# Paulo.net
KiCad netlist of a schematic drawn in EAGLE
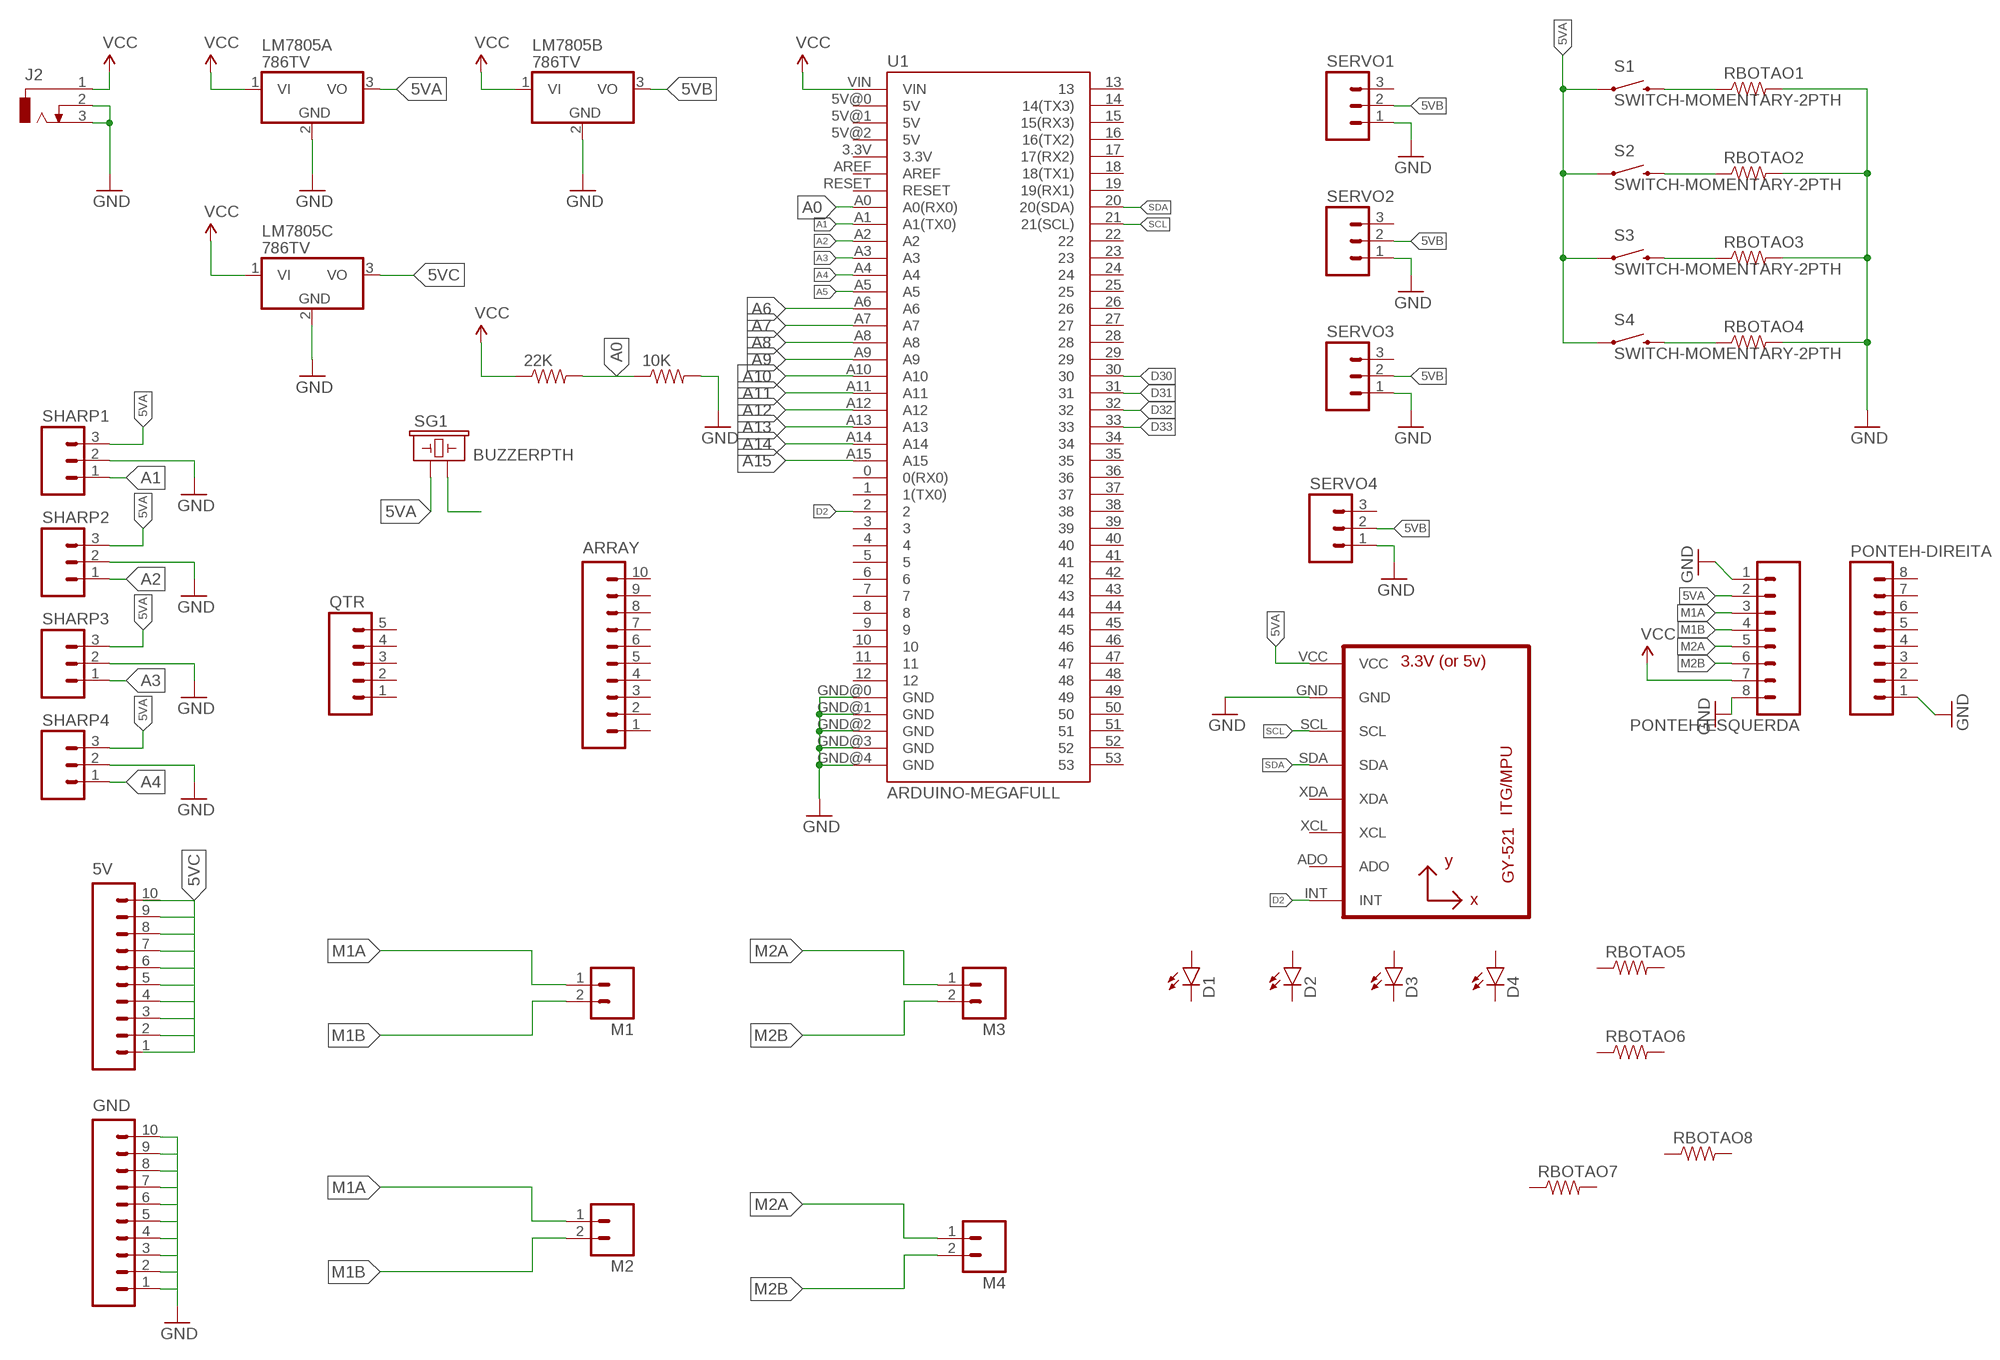
[diagram p0: schematic, sheet 1]

(export (version "E")
  (design (tool "Eeschema 10.0.6"))
  (components
    (comp (ref "5V")
      (value "M10SILK_FEMALE_PTH")
      (footprint "eagle-import:1X10")
      (libsource (lib "eagle-import") (part "M10SILK_FEMALE_PTH"))
    )
    (comp (ref "10K")
      (value "RESISTOREZ")
      (footprint "eagle-import:AXIAL-0.3EZ")
      (libsource (lib "eagle-import") (part "RESISTOREZ"))
    )
    (comp (ref "22K")
      (value "RESISTOREZ")
      (footprint "eagle-import:AXIAL-0.3EZ")
      (libsource (lib "eagle-import") (part "RESISTOREZ"))
    )
    (comp (ref "ARRAY")
      (value "M10SILK_FEMALE_PTH")
      (footprint "eagle-import:1X10")
      (libsource (lib "eagle-import") (part "M10SILK_FEMALE_PTH"))
    )
    (comp (ref "D1")
      (value "LED5MM")
      (footprint "eagle-import:LED5MM")
      (libsource (lib "eagle-import") (part "LED5MM"))
    )
    (comp (ref "D2")
      (value "LED5MM")
      (footprint "eagle-import:LED5MM")
      (libsource (lib "eagle-import") (part "LED5MM"))
    )
    (comp (ref "D3")
      (value "LED5MM")
      (footprint "eagle-import:LED5MM")
      (libsource (lib "eagle-import") (part "LED5MM"))
    )
    (comp (ref "D4")
      (value "LED5MM")
      (footprint "eagle-import:LED5MM")
      (libsource (lib "eagle-import") (part "LED5MM"))
    )
    (comp (ref "GND")
      (value "M10SILK_FEMALE_PTH")
      (footprint "eagle-import:1X10")
      (libsource (lib "eagle-import") (part "M10SILK_FEMALE_PTH"))
    )
    (comp (ref "J2")
      (value "DCJ0303")
      (footprint "eagle-import:DCJ0303")
      (libsource (lib "eagle-import") (part "DCJ0303"))
    )
    (comp (ref "LM7805A")
      (value "786TV")
      (footprint "eagle-import:TO220V")
      (libsource (lib "eagle-import") (part "78TV6"))
    )
    (comp (ref "LM7805B")
      (value "786TV")
      (footprint "eagle-import:TO220V")
      (libsource (lib "eagle-import") (part "78TV6"))
    )
    (comp (ref "LM7805C")
      (value "786TV")
      (footprint "eagle-import:TO220V")
      (libsource (lib "eagle-import") (part "78TV6"))
    )
    (comp (ref "M1")
      (value "M02JST-PTH-VERT")
      (footprint "eagle-import:JST-2-PTH-VERT")
      (libsource (lib "eagle-import") (part "M02JST-PTH-VERT"))
    )
    (comp (ref "M2")
      (value "M02JST-PTH-VERT")
      (footprint "eagle-import:JST-2-PTH-VERT")
      (libsource (lib "eagle-import") (part "M02JST-PTH-VERT"))
    )
    (comp (ref "M3")
      (value "M02JST-PTH-VERT")
      (footprint "eagle-import:JST-2-PTH-VERT")
      (libsource (lib "eagle-import") (part "M02JST-PTH-VERT"))
    )
    (comp (ref "M4")
      (value "M02JST-PTH-VERT")
      (footprint "eagle-import:JST-2-PTH-VERT")
      (libsource (lib "eagle-import") (part "M02JST-PTH-VERT"))
    )
    (comp (ref "PONTEH-DIREITA")
      (value "M08NO_SILK")
      (footprint "eagle-import:1X08_PIN1_NO_SILK")
      (libsource (lib "eagle-import") (part "M08NO_SILK"))
    )
    (comp (ref "PONTEH-ESQUERDA")
      (value "M08NO_SILK")
      (footprint "eagle-import:1X08_PIN1_NO_SILK")
      (libsource (lib "eagle-import") (part "M08NO_SILK"))
    )
    (comp (ref "QTR")
      (value "M05PTH_LONGPADS")
      (footprint "eagle-import:1X05_LONGPADS")
      (libsource (lib "eagle-import") (part "M05PTH_LONGPADS"))
    )
    (comp (ref "RBOTAO1")
      (value "RESISTOREZ")
      (footprint "eagle-import:AXIAL-0.3EZ")
      (libsource (lib "eagle-import") (part "RESISTOREZ"))
    )
    (comp (ref "RBOTAO2")
      (value "RESISTOREZ")
      (footprint "eagle-import:AXIAL-0.3EZ")
      (libsource (lib "eagle-import") (part "RESISTOREZ"))
    )
    (comp (ref "RBOTAO3")
      (value "RESISTOREZ")
      (footprint "eagle-import:AXIAL-0.3EZ")
      (libsource (lib "eagle-import") (part "RESISTOREZ"))
    )
    (comp (ref "RBOTAO4")
      (value "RESISTOREZ")
      (footprint "eagle-import:AXIAL-0.3EZ")
      (libsource (lib "eagle-import") (part "RESISTOREZ"))
    )
    (comp (ref "RBOTAO5")
      (value "RESISTOREZ")
      (footprint "eagle-import:AXIAL-0.3EZ")
      (libsource (lib "eagle-import") (part "RESISTOREZ"))
    )
    (comp (ref "RBOTAO6")
      (value "RESISTOREZ")
      (footprint "eagle-import:AXIAL-0.3EZ")
      (libsource (lib "eagle-import") (part "RESISTOREZ"))
    )
    (comp (ref "RBOTAO7")
      (value "RESISTOREZ")
      (footprint "eagle-import:AXIAL-0.3EZ")
      (libsource (lib "eagle-import") (part "RESISTOREZ"))
    )
    (comp (ref "RBOTAO8")
      (value "RESISTOREZ")
      (footprint "eagle-import:AXIAL-0.3EZ")
      (libsource (lib "eagle-import") (part "RESISTOREZ"))
    )
    (comp (ref "S1")
      (value "SWITCH-MOMENTARY-2PTH")
      (footprint "eagle-import:TACTILE-PTH")
      (libsource (lib "eagle-import") (part "SWITCH-MOMENTARY-2PTH"))
    )
    (comp (ref "S2")
      (value "SWITCH-MOMENTARY-2PTH")
      (footprint "eagle-import:TACTILE-PTH")
      (libsource (lib "eagle-import") (part "SWITCH-MOMENTARY-2PTH"))
    )
    (comp (ref "S3")
      (value "SWITCH-MOMENTARY-2PTH")
      (footprint "eagle-import:TACTILE-PTH")
      (libsource (lib "eagle-import") (part "SWITCH-MOMENTARY-2PTH"))
    )
    (comp (ref "S4")
      (value "SWITCH-MOMENTARY-2PTH")
      (footprint "eagle-import:TACTILE-PTH")
      (libsource (lib "eagle-import") (part "SWITCH-MOMENTARY-2PTH"))
    )
    (comp (ref "SERVO1")
      (value "M03LONGPADS")
      (footprint "eagle-import:1X03_LONGPADS")
      (libsource (lib "eagle-import") (part "M03LONGPADS"))
    )
    (comp (ref "SERVO2")
      (value "M03LONGPADS")
      (footprint "eagle-import:1X03_LONGPADS")
      (libsource (lib "eagle-import") (part "M03LONGPADS"))
    )
    (comp (ref "SERVO3")
      (value "M03LONGPADS")
      (footprint "eagle-import:1X03_LONGPADS")
      (libsource (lib "eagle-import") (part "M03LONGPADS"))
    )
    (comp (ref "SERVO4")
      (value "M03LONGPADS")
      (footprint "eagle-import:1X03_LONGPADS")
      (libsource (lib "eagle-import") (part "M03LONGPADS"))
    )
    (comp (ref "SG1")
      (value "BUZZERPTH")
      (footprint "eagle-import:BUZZER-12MM")
      (libsource (lib "eagle-import") (part "BUZZERPTH"))
    )
    (comp (ref "SHARP1")
      (value "M03LONGPADS")
      (footprint "eagle-import:1X03_LONGPADS")
      (libsource (lib "eagle-import") (part "M03LONGPADS"))
    )
    (comp (ref "SHARP2")
      (value "M03LONGPADS")
      (footprint "eagle-import:1X03_LONGPADS")
      (libsource (lib "eagle-import") (part "M03LONGPADS"))
    )
    (comp (ref "SHARP3")
      (value "M03LONGPADS")
      (footprint "eagle-import:1X03_LONGPADS")
      (libsource (lib "eagle-import") (part "M03LONGPADS"))
    )
    (comp (ref "SHARP4")
      (value "M03LONGPADS")
      (footprint "eagle-import:1X03_LONGPADS")
      (libsource (lib "eagle-import") (part "M03LONGPADS"))
    )
    (comp (ref "U1")
      (value "ARDUINO-MEGAFULL")
      (footprint "eagle-import:ARDUINO_MEGA")
      (libsource (lib "eagle-import") (part "ARDUINO-MEGAFULL"))
    )
    (comp (ref "U2")
      (value "GY-521MPU6050")
      (footprint "eagle-import:GY-521")
      (libsource (lib "eagle-import") (part "GY-521MPU6050"))
    )
  )
  (nets
    (net (code "1") (name "/D10") (class "Default")
      (node (ref "RBOTAO1") (pin "P$1") (pinfunction "1_P$1") (pintype "passive"))
      (node (ref "S1") (pin "3") (pinfunction "2_3") (pintype "passive"))
      (node (ref "SG1") (pin "-") (pinfunction "2_-") (pintype "passive"))
    )
    (net (code "2") (name "5VA") (class "Default")
      (node (ref "LM7805A") (pin "3") (pinfunction "VO_3") (pintype "passive"))
      (node (ref "PONTEH-ESQUERDA") (pin "2") (pinfunction "2_2") (pintype "passive"))
      (node (ref "S1") (pin "1") (pinfunction "1_1") (pintype "passive"))
      (node (ref "S2") (pin "1") (pinfunction "1_1") (pintype "passive"))
      (node (ref "S3") (pin "1") (pinfunction "1_1") (pintype "passive"))
      (node (ref "S4") (pin "1") (pinfunction "1_1") (pintype "passive"))
      (node (ref "SG1") (pin "+") (pinfunction "1_+") (pintype "passive"))
      (node (ref "SHARP1") (pin "3") (pinfunction "3_3") (pintype "passive"))
      (node (ref "SHARP2") (pin "3") (pinfunction "3_3") (pintype "passive"))
      (node (ref "SHARP3") (pin "3") (pinfunction "3_3") (pintype "passive"))
      (node (ref "SHARP4") (pin "3") (pinfunction "3_3") (pintype "passive"))
      (node (ref "U2") (pin "VCC") (pinfunction "VCC_VCC") (pintype "bidirectional"))
    )
    (net (code "3") (name "5VB") (class "Default")
      (node (ref "LM7805B") (pin "3") (pinfunction "VO_3") (pintype "passive"))
      (node (ref "SERVO1") (pin "2") (pinfunction "2_2") (pintype "passive"))
      (node (ref "SERVO2") (pin "2") (pinfunction "2_2") (pintype "passive"))
      (node (ref "SERVO3") (pin "2") (pinfunction "2_2") (pintype "passive"))
      (node (ref "SERVO4") (pin "2") (pinfunction "2_2") (pintype "passive"))
    )
    (net (code "4") (name "5VC") (class "Default")
      (node (ref "5V") (pin "2") (pinfunction "2_2") (pintype "passive"))
      (node (ref "5V") (pin "3") (pinfunction "3_3") (pintype "passive"))
      (node (ref "5V") (pin "4") (pinfunction "4_4") (pintype "passive"))
      (node (ref "5V") (pin "5") (pinfunction "5_5") (pintype "passive"))
      (node (ref "5V") (pin "6") (pinfunction "6_6") (pintype "passive"))
      (node (ref "5V") (pin "7") (pinfunction "7_7") (pintype "passive"))
      (node (ref "5V") (pin "8") (pinfunction "8_8") (pintype "passive"))
      (node (ref "5V") (pin "9") (pinfunction "9_9") (pintype "passive"))
      (node (ref "LM7805C") (pin "3") (pinfunction "VO_3") (pintype "passive"))
    )
    (net (code "5") (name "A0") (class "Default")
      (node (ref "10K") (pin "P$1") (pinfunction "1_P$1") (pintype "passive"))
      (node (ref "22K") (pin "P$2") (pinfunction "2_P$2") (pintype "passive"))
      (node (ref "U1") (pin "A0") (pinfunction "A0(RX0)_A0") (pintype "bidirectional"))
    )
    (net (code "6") (name "A1") (class "Default")
      (node (ref "SHARP1") (pin "1") (pinfunction "1_1") (pintype "passive"))
      (node (ref "U1") (pin "A1") (pinfunction "A1(TX0)_A1") (pintype "bidirectional"))
    )
    (net (code "7") (name "A2") (class "Default")
      (node (ref "SHARP2") (pin "1") (pinfunction "1_1") (pintype "passive"))
      (node (ref "U1") (pin "A2") (pinfunction "A2_A2") (pintype "bidirectional"))
    )
    (net (code "8") (name "A3") (class "Default")
      (node (ref "SHARP3") (pin "1") (pinfunction "1_1") (pintype "passive"))
      (node (ref "U1") (pin "A3") (pinfunction "A3_A3") (pintype "bidirectional"))
    )
    (net (code "9") (name "A4") (class "Default")
      (node (ref "SHARP4") (pin "1") (pinfunction "1_1") (pintype "passive"))
      (node (ref "U1") (pin "A4") (pinfunction "A4_A4") (pintype "bidirectional"))
    )
    (net (code "10") (name "A5") (class "Default")
      (node (ref "U1") (pin "A5") (pinfunction "A5_A5") (pintype "bidirectional"))
    )
    (net (code "11") (name "A6") (class "Default")
      (node (ref "U1") (pin "A6") (pinfunction "A6_A6") (pintype "bidirectional"))
    )
    (net (code "12") (name "A7") (class "Default")
      (node (ref "U1") (pin "A7") (pinfunction "A7_A7") (pintype "bidirectional"))
    )
    (net (code "13") (name "A8") (class "Default")
      (node (ref "U1") (pin "A8") (pinfunction "A8_A8") (pintype "bidirectional"))
    )
    (net (code "14") (name "A9") (class "Default")
      (node (ref "U1") (pin "A9") (pinfunction "A9_A9") (pintype "bidirectional"))
    )
    (net (code "15") (name "A10") (class "Default")
      (node (ref "U1") (pin "A10") (pinfunction "A10_A10") (pintype "bidirectional"))
    )
    (net (code "16") (name "A11") (class "Default")
      (node (ref "U1") (pin "A11") (pinfunction "A11_A11") (pintype "bidirectional"))
    )
    (net (code "17") (name "A12") (class "Default")
      (node (ref "U1") (pin "A12") (pinfunction "A12_A12") (pintype "bidirectional"))
    )
    (net (code "18") (name "A13") (class "Default")
      (node (ref "U1") (pin "A13") (pinfunction "A13_A13") (pintype "bidirectional"))
    )
    (net (code "19") (name "A14") (class "Default")
      (node (ref "U1") (pin "A14") (pinfunction "A14_A14") (pintype "bidirectional"))
    )
    (net (code "20") (name "A15") (class "Default")
      (node (ref "U1") (pin "A15") (pinfunction "A15_A15") (pintype "bidirectional"))
    )
    (net (code "21") (name "D2") (class "Default")
      (node (ref "U1") (pin "2") (pinfunction "2_2") (pintype "bidirectional"))
      (node (ref "U2") (pin "INT") (pinfunction "INT_INT") (pintype "bidirectional"))
    )
    (net (code "22") (name "D30") (class "Default")
      (node (ref "U1") (pin "30") (pinfunction "30_30") (pintype "bidirectional"))
    )
    (net (code "23") (name "D31") (class "Default")
      (node (ref "U1") (pin "31") (pinfunction "31_31") (pintype "bidirectional"))
    )
    (net (code "24") (name "D32") (class "Default")
      (node (ref "U1") (pin "32") (pinfunction "32_32") (pintype "bidirectional"))
    )
    (net (code "25") (name "D33") (class "Default")
      (node (ref "U1") (pin "33") (pinfunction "33_33") (pintype "bidirectional"))
    )
    (net (code "26") (name "GND") (class "Default")
      (node (ref "10K") (pin "P$2") (pinfunction "2_P$2") (pintype "passive"))
      (node (ref "GND") (pin "1") (pinfunction "1_1") (pintype "passive"))
      (node (ref "GND") (pin "10") (pinfunction "10_10") (pintype "passive"))
      (node (ref "GND") (pin "2") (pinfunction "2_2") (pintype "passive"))
      (node (ref "GND") (pin "3") (pinfunction "3_3") (pintype "passive"))
      (node (ref "GND") (pin "4") (pinfunction "4_4") (pintype "passive"))
      (node (ref "GND") (pin "5") (pinfunction "5_5") (pintype "passive"))
      (node (ref "GND") (pin "6") (pinfunction "6_6") (pintype "passive"))
      (node (ref "GND") (pin "7") (pinfunction "7_7") (pintype "passive"))
      (node (ref "GND") (pin "8") (pinfunction "8_8") (pintype "passive"))
      (node (ref "GND") (pin "9") (pinfunction "9_9") (pintype "passive"))
      (node (ref "J2") (pin "2") (pinfunction "2_2") (pintype "passive"))
      (node (ref "J2") (pin "3") (pinfunction "3_3") (pintype "passive"))
      (node (ref "LM7805A") (pin "2") (pinfunction "GND_2") (pintype "passive"))
      (node (ref "LM7805B") (pin "2") (pinfunction "GND_2") (pintype "passive"))
      (node (ref "LM7805C") (pin "2") (pinfunction "GND_2") (pintype "passive"))
      (node (ref "PONTEH-DIREITA") (pin "1") (pinfunction "1_1") (pintype "passive"))
      (node (ref "PONTEH-ESQUERDA") (pin "1") (pinfunction "1_1") (pintype "passive"))
      (node (ref "PONTEH-ESQUERDA") (pin "8") (pinfunction "8_8") (pintype "passive"))
      (node (ref "RBOTAO1") (pin "P$2") (pinfunction "2_P$2") (pintype "passive"))
      (node (ref "RBOTAO2") (pin "P$2") (pinfunction "2_P$2") (pintype "passive"))
      (node (ref "RBOTAO3") (pin "P$2") (pinfunction "2_P$2") (pintype "passive"))
      (node (ref "RBOTAO4") (pin "P$2") (pinfunction "2_P$2") (pintype "passive"))
      (node (ref "SERVO1") (pin "1") (pinfunction "1_1") (pintype "passive"))
      (node (ref "SERVO2") (pin "1") (pinfunction "1_1") (pintype "passive"))
      (node (ref "SERVO3") (pin "1") (pinfunction "1_1") (pintype "passive"))
      (node (ref "SERVO4") (pin "1") (pinfunction "1_1") (pintype "passive"))
      (node (ref "SHARP1") (pin "2") (pinfunction "2_2") (pintype "passive"))
      (node (ref "SHARP2") (pin "2") (pinfunction "2_2") (pintype "passive"))
      (node (ref "SHARP3") (pin "2") (pinfunction "2_2") (pintype "passive"))
      (node (ref "SHARP4") (pin "2") (pinfunction "2_2") (pintype "passive"))
      (node (ref "U1") (pin "GND@0") (pinfunction "GND_GND@0") (pintype "bidirectional"))
      (node (ref "U1") (pin "GND@1") (pinfunction "GND_GND@1") (pintype "bidirectional"))
      (node (ref "U1") (pin "GND@2") (pinfunction "GND_GND@2") (pintype "bidirectional"))
      (node (ref "U1") (pin "GND@3") (pinfunction "GND_GND@3") (pintype "bidirectional"))
      (node (ref "U1") (pin "GND@4") (pinfunction "GND_GND@4") (pintype "bidirectional"))
      (node (ref "U2") (pin "GND") (pinfunction "GND_GND") (pintype "bidirectional"))
    )
    (net (code "27") (name "M1A") (class "Default")
      (node (ref "M1") (pin "1") (pinfunction "1_1") (pintype "passive"))
      (node (ref "M2") (pin "1") (pinfunction "1_1") (pintype "passive"))
      (node (ref "PONTEH-ESQUERDA") (pin "3") (pinfunction "3_3") (pintype "passive"))
    )
    (net (code "28") (name "M1B") (class "Default")
      (node (ref "M1") (pin "2") (pinfunction "2_2") (pintype "passive"))
      (node (ref "M2") (pin "2") (pinfunction "2_2") (pintype "passive"))
      (node (ref "PONTEH-ESQUERDA") (pin "4") (pinfunction "4_4") (pintype "passive"))
    )
    (net (code "29") (name "M2A") (class "Default")
      (node (ref "M3") (pin "1") (pinfunction "1_1") (pintype "passive"))
      (node (ref "M4") (pin "1") (pinfunction "1_1") (pintype "passive"))
      (node (ref "PONTEH-ESQUERDA") (pin "5") (pinfunction "5_5") (pintype "passive"))
    )
    (net (code "30") (name "M2B") (class "Default")
      (node (ref "M3") (pin "2") (pinfunction "2_2") (pintype "passive"))
      (node (ref "M4") (pin "2") (pinfunction "2_2") (pintype "passive"))
      (node (ref "PONTEH-ESQUERDA") (pin "6") (pinfunction "6_6") (pintype "passive"))
    )
    (net (code "31") (name "Net-(RBOTAO2-1)") (class "Default")
      (node (ref "RBOTAO2") (pin "P$1") (pinfunction "1_P$1") (pintype "passive"))
      (node (ref "S2") (pin "3") (pinfunction "2_3") (pintype "passive"))
    )
    (net (code "32") (name "Net-(RBOTAO3-1)") (class "Default")
      (node (ref "RBOTAO3") (pin "P$1") (pinfunction "1_P$1") (pintype "passive"))
      (node (ref "S3") (pin "3") (pinfunction "2_3") (pintype "passive"))
    )
    (net (code "33") (name "Net-(RBOTAO4-1)") (class "Default")
      (node (ref "RBOTAO4") (pin "P$1") (pinfunction "1_P$1") (pintype "passive"))
      (node (ref "S4") (pin "3") (pinfunction "2_3") (pintype "passive"))
    )
    (net (code "34") (name "SCL") (class "Default")
      (node (ref "U1") (pin "21") (pinfunction "21(SCL)_21") (pintype "bidirectional"))
      (node (ref "U2") (pin "SCL") (pinfunction "SCL_SCL") (pintype "bidirectional"))
    )
    (net (code "35") (name "SDA") (class "Default")
      (node (ref "U1") (pin "20") (pinfunction "20(SDA)_20") (pintype "bidirectional"))
      (node (ref "U2") (pin "SDA") (pinfunction "SDA_SDA") (pintype "bidirectional"))
    )
    (net (code "36") (name "VCC") (class "Default")
      (node (ref "22K") (pin "P$1") (pinfunction "1_P$1") (pintype "passive"))
      (node (ref "J2") (pin "1") (pinfunction "1_1") (pintype "passive"))
      (node (ref "LM7805A") (pin "1") (pinfunction "VI_1") (pintype "input"))
      (node (ref "LM7805B") (pin "1") (pinfunction "VI_1") (pintype "input"))
      (node (ref "LM7805C") (pin "1") (pinfunction "VI_1") (pintype "input"))
      (node (ref "PONTEH-ESQUERDA") (pin "7") (pinfunction "7_7") (pintype "passive"))
      (node (ref "U1") (pin "VIN") (pinfunction "VIN_VIN") (pintype "bidirectional"))
    )
    (net (code "37") (name "unconnected-(5V-Pad1)") (class "Default")
      (node (ref "5V") (pin "1") (pinfunction "1_1") (pintype "passive"))
    )
    (net (code "38") (name "unconnected-(5V-Pad10)") (class "Default")
      (node (ref "5V") (pin "10") (pinfunction "10_10") (pintype "passive"))
    )
    (net (code "39") (name "unconnected-(ARRAY-Pad1)") (class "Default")
      (node (ref "ARRAY") (pin "1") (pinfunction "1_1") (pintype "passive"))
    )
    (net (code "40") (name "unconnected-(ARRAY-Pad2)") (class "Default")
      (node (ref "ARRAY") (pin "2") (pinfunction "2_2") (pintype "passive"))
    )
    (net (code "41") (name "unconnected-(ARRAY-Pad3)") (class "Default")
      (node (ref "ARRAY") (pin "3") (pinfunction "3_3") (pintype "passive"))
    )
    (net (code "42") (name "unconnected-(ARRAY-Pad4)") (class "Default")
      (node (ref "ARRAY") (pin "4") (pinfunction "4_4") (pintype "passive"))
    )
    (net (code "43") (name "unconnected-(ARRAY-Pad5)") (class "Default")
      (node (ref "ARRAY") (pin "5") (pinfunction "5_5") (pintype "passive"))
    )
    (net (code "44") (name "unconnected-(ARRAY-Pad6)") (class "Default")
      (node (ref "ARRAY") (pin "6") (pinfunction "6_6") (pintype "passive"))
    )
    (net (code "45") (name "unconnected-(ARRAY-Pad7)") (class "Default")
      (node (ref "ARRAY") (pin "7") (pinfunction "7_7") (pintype "passive"))
    )
    (net (code "46") (name "unconnected-(ARRAY-Pad8)") (class "Default")
      (node (ref "ARRAY") (pin "8") (pinfunction "8_8") (pintype "passive"))
    )
    (net (code "47") (name "unconnected-(ARRAY-Pad9)") (class "Default")
      (node (ref "ARRAY") (pin "9") (pinfunction "9_9") (pintype "passive"))
    )
    (net (code "48") (name "unconnected-(ARRAY-Pad10)") (class "Default")
      (node (ref "ARRAY") (pin "10") (pinfunction "10_10") (pintype "passive"))
    )
    (net (code "49") (name "unconnected-(D1-C-PadK)") (class "Default")
      (node (ref "D1") (pin "K") (pinfunction "C_K") (pintype "passive"))
    )
    (net (code "50") (name "unconnected-(D1-PadA)") (class "Default")
      (node (ref "D1") (pin "A") (pinfunction "A_A") (pintype "passive"))
    )
    (net (code "51") (name "unconnected-(D2-C-PadK)") (class "Default")
      (node (ref "D2") (pin "K") (pinfunction "C_K") (pintype "passive"))
    )
    (net (code "52") (name "unconnected-(D2-PadA)") (class "Default")
      (node (ref "D2") (pin "A") (pinfunction "A_A") (pintype "passive"))
    )
    (net (code "53") (name "unconnected-(D3-C-PadK)") (class "Default")
      (node (ref "D3") (pin "K") (pinfunction "C_K") (pintype "passive"))
    )
    (net (code "54") (name "unconnected-(D3-PadA)") (class "Default")
      (node (ref "D3") (pin "A") (pinfunction "A_A") (pintype "passive"))
    )
    (net (code "55") (name "unconnected-(D4-C-PadK)") (class "Default")
      (node (ref "D4") (pin "K") (pinfunction "C_K") (pintype "passive"))
    )
    (net (code "56") (name "unconnected-(D4-PadA)") (class "Default")
      (node (ref "D4") (pin "A") (pinfunction "A_A") (pintype "passive"))
    )
    (net (code "57") (name "unconnected-(PONTEH-DIREITA-Pad2)") (class "Default")
      (node (ref "PONTEH-DIREITA") (pin "2") (pinfunction "2_2") (pintype "passive"))
    )
    (net (code "58") (name "unconnected-(PONTEH-DIREITA-Pad3)") (class "Default")
      (node (ref "PONTEH-DIREITA") (pin "3") (pinfunction "3_3") (pintype "passive"))
    )
    (net (code "59") (name "unconnected-(PONTEH-DIREITA-Pad4)") (class "Default")
      (node (ref "PONTEH-DIREITA") (pin "4") (pinfunction "4_4") (pintype "passive"))
    )
    (net (code "60") (name "unconnected-(PONTEH-DIREITA-Pad5)") (class "Default")
      (node (ref "PONTEH-DIREITA") (pin "5") (pinfunction "5_5") (pintype "passive"))
    )
    (net (code "61") (name "unconnected-(PONTEH-DIREITA-Pad6)") (class "Default")
      (node (ref "PONTEH-DIREITA") (pin "6") (pinfunction "6_6") (pintype "passive"))
    )
    (net (code "62") (name "unconnected-(PONTEH-DIREITA-Pad7)") (class "Default")
      (node (ref "PONTEH-DIREITA") (pin "7") (pinfunction "7_7") (pintype "passive"))
    )
    (net (code "63") (name "unconnected-(PONTEH-DIREITA-Pad8)") (class "Default")
      (node (ref "PONTEH-DIREITA") (pin "8") (pinfunction "8_8") (pintype "passive"))
    )
    (net (code "64") (name "unconnected-(QTR-Pad1)") (class "Default")
      (node (ref "QTR") (pin "1") (pinfunction "1_1") (pintype "passive"))
    )
    (net (code "65") (name "unconnected-(QTR-Pad2)") (class "Default")
      (node (ref "QTR") (pin "2") (pinfunction "2_2") (pintype "passive"))
    )
    (net (code "66") (name "unconnected-(QTR-Pad3)") (class "Default")
      (node (ref "QTR") (pin "3") (pinfunction "3_3") (pintype "passive"))
    )
    (net (code "67") (name "unconnected-(QTR-Pad4)") (class "Default")
      (node (ref "QTR") (pin "4") (pinfunction "4_4") (pintype "passive"))
    )
    (net (code "68") (name "unconnected-(QTR-Pad5)") (class "Default")
      (node (ref "QTR") (pin "5") (pinfunction "5_5") (pintype "passive"))
    )
    (net (code "69") (name "unconnected-(RBOTAO5-1-PadP$1)") (class "Default")
      (node (ref "RBOTAO5") (pin "P$1") (pinfunction "1_P$1") (pintype "passive"))
    )
    (net (code "70") (name "unconnected-(RBOTAO5-2-PadP$2)") (class "Default")
      (node (ref "RBOTAO5") (pin "P$2") (pinfunction "2_P$2") (pintype "passive"))
    )
    (net (code "71") (name "unconnected-(RBOTAO6-1-PadP$1)") (class "Default")
      (node (ref "RBOTAO6") (pin "P$1") (pinfunction "1_P$1") (pintype "passive"))
    )
    (net (code "72") (name "unconnected-(RBOTAO6-2-PadP$2)") (class "Default")
      (node (ref "RBOTAO6") (pin "P$2") (pinfunction "2_P$2") (pintype "passive"))
    )
    (net (code "73") (name "unconnected-(RBOTAO7-1-PadP$1)") (class "Default")
      (node (ref "RBOTAO7") (pin "P$1") (pinfunction "1_P$1") (pintype "passive"))
    )
    (net (code "74") (name "unconnected-(RBOTAO7-2-PadP$2)") (class "Default")
      (node (ref "RBOTAO7") (pin "P$2") (pinfunction "2_P$2") (pintype "passive"))
    )
    (net (code "75") (name "unconnected-(RBOTAO8-1-PadP$1)") (class "Default")
      (node (ref "RBOTAO8") (pin "P$1") (pinfunction "1_P$1") (pintype "passive"))
    )
    (net (code "76") (name "unconnected-(RBOTAO8-2-PadP$2)") (class "Default")
      (node (ref "RBOTAO8") (pin "P$2") (pinfunction "2_P$2") (pintype "passive"))
    )
    (net (code "77") (name "unconnected-(SERVO1-Pad3)") (class "Default")
      (node (ref "SERVO1") (pin "3") (pinfunction "3_3") (pintype "passive"))
    )
    (net (code "78") (name "unconnected-(SERVO2-Pad3)") (class "Default")
      (node (ref "SERVO2") (pin "3") (pinfunction "3_3") (pintype "passive"))
    )
    (net (code "79") (name "unconnected-(SERVO3-Pad3)") (class "Default")
      (node (ref "SERVO3") (pin "3") (pinfunction "3_3") (pintype "passive"))
    )
    (net (code "80") (name "unconnected-(SERVO4-Pad3)") (class "Default")
      (node (ref "SERVO4") (pin "3") (pinfunction "3_3") (pintype "passive"))
    )
    (net (code "81") (name "unconnected-(U1-0(RX0)-Pad0)") (class "Default")
      (node (ref "U1") (pin "0") (pinfunction "0(RX0)_0") (pintype "bidirectional"))
    )
    (net (code "82") (name "unconnected-(U1-1(TX0)-Pad1)") (class "Default")
      (node (ref "U1") (pin "1") (pinfunction "1(TX0)_1") (pintype "bidirectional"))
    )
    (net (code "83") (name "unconnected-(U1-5V-Pad5V@0)") (class "Default")
      (node (ref "U1") (pin "5V@0") (pinfunction "5V_5V@0") (pintype "bidirectional"))
    )
    (net (code "84") (name "unconnected-(U1-5V-Pad5V@1)") (class "Default")
      (node (ref "U1") (pin "5V@1") (pinfunction "5V_5V@1") (pintype "bidirectional"))
    )
    (net (code "85") (name "unconnected-(U1-5V-Pad5V@2)") (class "Default")
      (node (ref "U1") (pin "5V@2") (pinfunction "5V_5V@2") (pintype "bidirectional"))
    )
    (net (code "86") (name "unconnected-(U1-14(TX3)-Pad14)") (class "Default")
      (node (ref "U1") (pin "14") (pinfunction "14(TX3)_14") (pintype "bidirectional"))
    )
    (net (code "87") (name "unconnected-(U1-15(RX3)-Pad15)") (class "Default")
      (node (ref "U1") (pin "15") (pinfunction "15(RX3)_15") (pintype "bidirectional"))
    )
    (net (code "88") (name "unconnected-(U1-16(TX2)-Pad16)") (class "Default")
      (node (ref "U1") (pin "16") (pinfunction "16(TX2)_16") (pintype "bidirectional"))
    )
    (net (code "89") (name "unconnected-(U1-17(RX2)-Pad17)") (class "Default")
      (node (ref "U1") (pin "17") (pinfunction "17(RX2)_17") (pintype "bidirectional"))
    )
    (net (code "90") (name "unconnected-(U1-18(TX1)-Pad18)") (class "Default")
      (node (ref "U1") (pin "18") (pinfunction "18(TX1)_18") (pintype "bidirectional"))
    )
    (net (code "91") (name "unconnected-(U1-19(RX1)-Pad19)") (class "Default")
      (node (ref "U1") (pin "19") (pinfunction "19(RX1)_19") (pintype "bidirectional"))
    )
    (net (code "92") (name "unconnected-(U1-Pad3)") (class "Default")
      (node (ref "U1") (pin "3") (pinfunction "3_3") (pintype "bidirectional"))
    )
    (net (code "93") (name "unconnected-(U1-Pad3.3V)") (class "Default")
      (node (ref "U1") (pin "3.3V") (pinfunction "3.3V_3.3V") (pintype "bidirectional"))
    )
    (net (code "94") (name "unconnected-(U1-Pad4)") (class "Default")
      (node (ref "U1") (pin "4") (pinfunction "4_4") (pintype "bidirectional"))
    )
    (net (code "95") (name "unconnected-(U1-Pad5)") (class "Default")
      (node (ref "U1") (pin "5") (pinfunction "5_5") (pintype "bidirectional"))
    )
    (net (code "96") (name "unconnected-(U1-Pad6)") (class "Default")
      (node (ref "U1") (pin "6") (pinfunction "6_6") (pintype "bidirectional"))
    )
    (net (code "97") (name "unconnected-(U1-Pad7)") (class "Default")
      (node (ref "U1") (pin "7") (pinfunction "7_7") (pintype "bidirectional"))
    )
    (net (code "98") (name "unconnected-(U1-Pad8)") (class "Default")
      (node (ref "U1") (pin "8") (pinfunction "8_8") (pintype "bidirectional"))
    )
    (net (code "99") (name "unconnected-(U1-Pad9)") (class "Default")
      (node (ref "U1") (pin "9") (pinfunction "9_9") (pintype "bidirectional"))
    )
    (net (code "100") (name "unconnected-(U1-Pad10)") (class "Default")
      (node (ref "U1") (pin "10") (pinfunction "10_10") (pintype "bidirectional"))
    )
    (net (code "101") (name "unconnected-(U1-Pad11)") (class "Default")
      (node (ref "U1") (pin "11") (pinfunction "11_11") (pintype "bidirectional"))
    )
    (net (code "102") (name "unconnected-(U1-Pad12)") (class "Default")
      (node (ref "U1") (pin "12") (pinfunction "12_12") (pintype "bidirectional"))
    )
    (net (code "103") (name "unconnected-(U1-Pad13)") (class "Default")
      (node (ref "U1") (pin "13") (pinfunction "13_13") (pintype "bidirectional"))
    )
    (net (code "104") (name "unconnected-(U1-Pad22)") (class "Default")
      (node (ref "U1") (pin "22") (pinfunction "22_22") (pintype "bidirectional"))
    )
    (net (code "105") (name "unconnected-(U1-Pad23)") (class "Default")
      (node (ref "U1") (pin "23") (pinfunction "23_23") (pintype "bidirectional"))
    )
    (net (code "106") (name "unconnected-(U1-Pad24)") (class "Default")
      (node (ref "U1") (pin "24") (pinfunction "24_24") (pintype "bidirectional"))
    )
    (net (code "107") (name "unconnected-(U1-Pad25)") (class "Default")
      (node (ref "U1") (pin "25") (pinfunction "25_25") (pintype "bidirectional"))
    )
    (net (code "108") (name "unconnected-(U1-Pad26)") (class "Default")
      (node (ref "U1") (pin "26") (pinfunction "26_26") (pintype "bidirectional"))
    )
    (net (code "109") (name "unconnected-(U1-Pad27)") (class "Default")
      (node (ref "U1") (pin "27") (pinfunction "27_27") (pintype "bidirectional"))
    )
    (net (code "110") (name "unconnected-(U1-Pad28)") (class "Default")
      (node (ref "U1") (pin "28") (pinfunction "28_28") (pintype "bidirectional"))
    )
    (net (code "111") (name "unconnected-(U1-Pad29)") (class "Default")
      (node (ref "U1") (pin "29") (pinfunction "29_29") (pintype "bidirectional"))
    )
    (net (code "112") (name "unconnected-(U1-Pad34)") (class "Default")
      (node (ref "U1") (pin "34") (pinfunction "34_34") (pintype "bidirectional"))
    )
    (net (code "113") (name "unconnected-(U1-Pad35)") (class "Default")
      (node (ref "U1") (pin "35") (pinfunction "35_35") (pintype "bidirectional"))
    )
    (net (code "114") (name "unconnected-(U1-Pad36)") (class "Default")
      (node (ref "U1") (pin "36") (pinfunction "36_36") (pintype "bidirectional"))
    )
    (net (code "115") (name "unconnected-(U1-Pad37)") (class "Default")
      (node (ref "U1") (pin "37") (pinfunction "37_37") (pintype "bidirectional"))
    )
    (net (code "116") (name "unconnected-(U1-Pad38)") (class "Default")
      (node (ref "U1") (pin "38") (pinfunction "38_38") (pintype "bidirectional"))
    )
    (net (code "117") (name "unconnected-(U1-Pad39)") (class "Default")
      (node (ref "U1") (pin "39") (pinfunction "39_39") (pintype "bidirectional"))
    )
    (net (code "118") (name "unconnected-(U1-Pad40)") (class "Default")
      (node (ref "U1") (pin "40") (pinfunction "40_40") (pintype "bidirectional"))
    )
    (net (code "119") (name "unconnected-(U1-Pad41)") (class "Default")
      (node (ref "U1") (pin "41") (pinfunction "41_41") (pintype "bidirectional"))
    )
    (net (code "120") (name "unconnected-(U1-Pad42)") (class "Default")
      (node (ref "U1") (pin "42") (pinfunction "42_42") (pintype "bidirectional"))
    )
    (net (code "121") (name "unconnected-(U1-Pad43)") (class "Default")
      (node (ref "U1") (pin "43") (pinfunction "43_43") (pintype "bidirectional"))
    )
    (net (code "122") (name "unconnected-(U1-Pad44)") (class "Default")
      (node (ref "U1") (pin "44") (pinfunction "44_44") (pintype "bidirectional"))
    )
    (net (code "123") (name "unconnected-(U1-Pad45)") (class "Default")
      (node (ref "U1") (pin "45") (pinfunction "45_45") (pintype "bidirectional"))
    )
    (net (code "124") (name "unconnected-(U1-Pad46)") (class "Default")
      (node (ref "U1") (pin "46") (pinfunction "46_46") (pintype "bidirectional"))
    )
    (net (code "125") (name "unconnected-(U1-Pad47)") (class "Default")
      (node (ref "U1") (pin "47") (pinfunction "47_47") (pintype "bidirectional"))
    )
    (net (code "126") (name "unconnected-(U1-Pad48)") (class "Default")
      (node (ref "U1") (pin "48") (pinfunction "48_48") (pintype "bidirectional"))
    )
    (net (code "127") (name "unconnected-(U1-Pad49)") (class "Default")
      (node (ref "U1") (pin "49") (pinfunction "49_49") (pintype "bidirectional"))
    )
    (net (code "128") (name "unconnected-(U1-Pad50)") (class "Default")
      (node (ref "U1") (pin "50") (pinfunction "50_50") (pintype "bidirectional"))
    )
    (net (code "129") (name "unconnected-(U1-Pad51)") (class "Default")
      (node (ref "U1") (pin "51") (pinfunction "51_51") (pintype "bidirectional"))
    )
    (net (code "130") (name "unconnected-(U1-Pad52)") (class "Default")
      (node (ref "U1") (pin "52") (pinfunction "52_52") (pintype "bidirectional"))
    )
    (net (code "131") (name "unconnected-(U1-Pad53)") (class "Default")
      (node (ref "U1") (pin "53") (pinfunction "53_53") (pintype "bidirectional"))
    )
    (net (code "132") (name "unconnected-(U1-PadAREF)") (class "Default")
      (node (ref "U1") (pin "AREF") (pinfunction "AREF_AREF") (pintype "bidirectional"))
    )
    (net (code "133") (name "unconnected-(U1-PadRESET)") (class "Default")
      (node (ref "U1") (pin "RESET") (pinfunction "RESET_RESET") (pintype "bidirectional"))
    )
    (net (code "134") (name "unconnected-(U2-PadADO)") (class "Default")
      (node (ref "U2") (pin "ADO") (pinfunction "ADO_ADO") (pintype "bidirectional"))
    )
    (net (code "135") (name "unconnected-(U2-PadXCL)") (class "Default")
      (node (ref "U2") (pin "XCL") (pinfunction "XCL_XCL") (pintype "bidirectional"))
    )
    (net (code "136") (name "unconnected-(U2-PadXDA)") (class "Default")
      (node (ref "U2") (pin "XDA") (pinfunction "XDA_XDA") (pintype "bidirectional"))
    )
  )
)
